# nguon5v_sch.net
KiCad netlist of a schematic drawn in Altium Designer
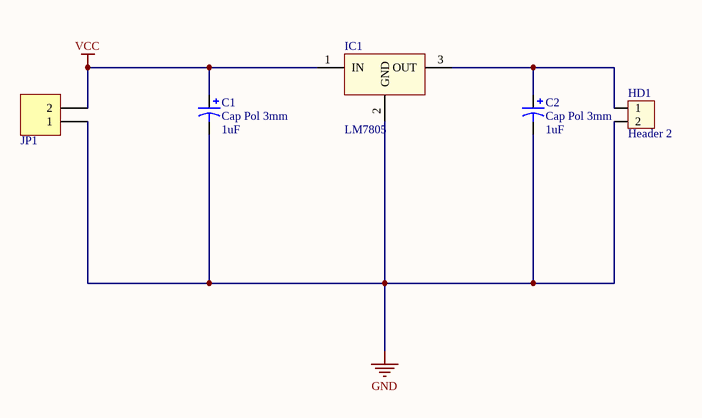
[diagram p0: nguon5v sch.SchDoc]

(export (version "E")
  (design (tool "Eeschema 10.0.6"))
  (components
    (comp (ref "C1")
      (value "Cap Pol 3mm")
      (footprint "C3MM")
      (description "Polarized Capacitor (Axial)")
      (fields (field (name "ALTIUM_UNNAMED_1") "1uF") (field (name "PUBLISHER") "Altium Limited"))
      (libsource (lib "My Library") (part "Cap Pol 3mm"))
    )
    (comp (ref "C2")
      (value "Cap Pol 3mm")
      (footprint "C3MM")
      (description "Polarized Capacitor (Axial)")
      (fields (field (name "ALTIUM_UNNAMED_1") "1uF") (field (name "PUBLISHER") "Altium Limited"))
      (libsource (lib "My Library") (part "Cap Pol 3mm"))
    )
    (comp (ref "HD1")
      (value "Header 2")
      (footprint "HED2")
      (description "Header 2 (Green)")
      (libsource (lib "syhaunguyen") (part "Hed2"))
    )
    (comp (ref "IC1")
      (value "LM7805")
      (footprint "QTO-220")
      (description "On ap +, from + 5 to + 24VDC")
      (libsource (lib "syhaunguyen") (part "LM78xx"))
    )
    (comp (ref "JP1")
      (value "Header 2_1")
      (footprint "HED2")
      (description "Header, 2-Pin")
      (fields (field (name "MANUFACTURER") "Generic Components"))
      (libsource (lib "syhaunguyen") (part "Header 2_1"))
    )
  )
  (nets
    (net (code "1") (name "GND") (class "Default")
      (node (ref "C1") (pin "2") (pinfunction "2_2") (pintype "passive"))
      (node (ref "C2") (pin "2") (pinfunction "2_2") (pintype "passive"))
      (node (ref "HD1") (pin "2") (pinfunction "2_2") (pintype "passive"))
      (node (ref "IC1") (pin "2") (pinfunction "GND_2") (pintype "passive"))
      (node (ref "JP1") (pin "1") (pinfunction "1_1") (pintype "passive"))
    )
    (net (code "2") (name "Net-(IC1-OUT)") (class "Default")
      (node (ref "C2") (pin "1") (pinfunction "1_1") (pintype "passive"))
      (node (ref "HD1") (pin "1") (pinfunction "1_1") (pintype "passive"))
      (node (ref "IC1") (pin "3") (pinfunction "OUT_3") (pintype "passive"))
    )
    (net (code "3") (name "VCC") (class "Default")
      (node (ref "C1") (pin "1") (pinfunction "1_1") (pintype "passive"))
      (node (ref "IC1") (pin "1") (pinfunction "IN_1") (pintype "passive"))
      (node (ref "JP1") (pin "2") (pinfunction "2_2") (pintype "passive"))
    )
  )
)
